# 6_power.net
KiCad netlist of a schematic drawn in Altium Designer
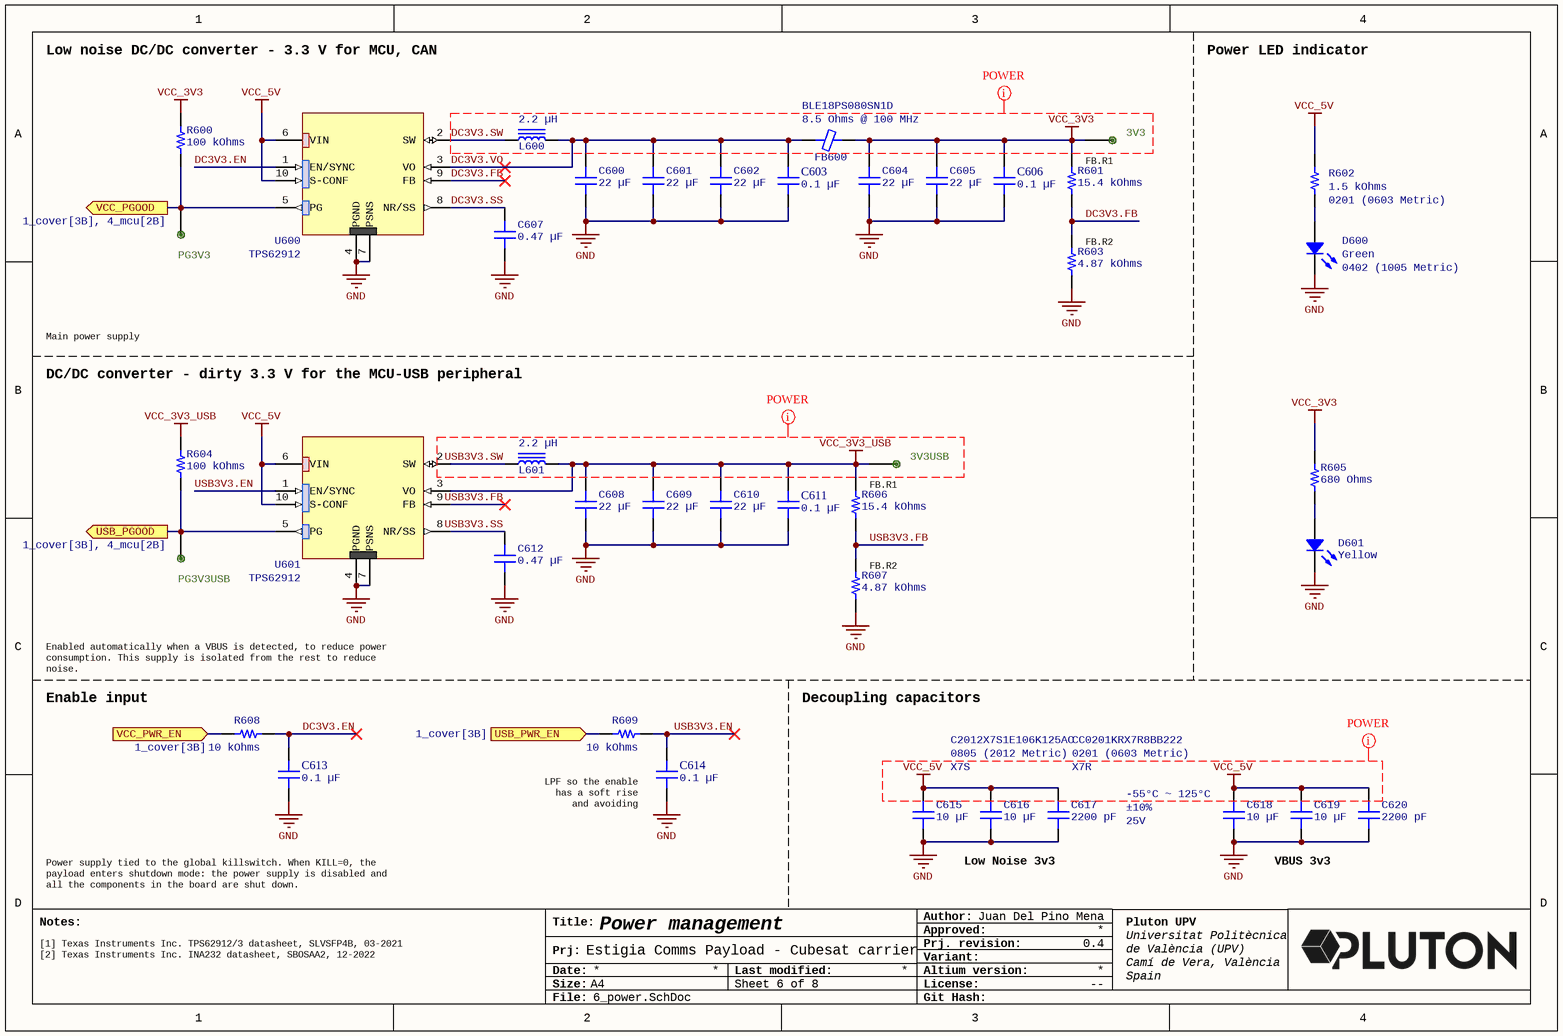
[diagram p0: 6_power.SchDoc]

(export (version "E")
  (design (tool "Eeschema 10.0.6"))
  (components
    (comp (ref "3V3")
      (value "~")
      (footprint "testpoints:testpoint_via")
      (description "Test point, thru-hole")
      (libsource (lib "testpoints") (part "TestPoint-VIA"))
    )
    (comp (ref "3V3USB")
      (value "~")
      (footprint "testpoints:testpoint_via")
      (description "Test point, thru-hole")
      (libsource (lib "testpoints") (part "TestPoint-VIA"))
    )
    (comp (ref "C600")
      (value "22 µF")
      (footprint "CAP 0805_2012")
      (description "CAP CER 22UF 10V X7S 0805")
      (fields
        (field (name "PART NUMBER") "C2012X7S1A226M125AC")
        (field (name "MANUFACTURER") "TDK Corporation")
      )
      (libsource (lib "Celestial Altium Library - altium_library") (part "Capacitor"))
    )
    (comp (ref "C601")
      (value "22 µF")
      (footprint "CAP 0805_2012")
      (description "CAP CER 22UF 10V X7S 0805")
      (fields
        (field (name "PART NUMBER") "C2012X7S1A226M125AC")
        (field (name "MANUFACTURER") "TDK Corporation")
      )
      (libsource (lib "Celestial Altium Library - altium_library") (part "Capacitor"))
    )
    (comp (ref "C602")
      (value "22 µF")
      (footprint "CAP 0805_2012")
      (description "CAP CER 22UF 10V X7S 0805")
      (fields
        (field (name "PART NUMBER") "C2012X7S1A226M125AC")
        (field (name "MANUFACTURER") "TDK Corporation")
      )
      (libsource (lib "Celestial Altium Library - altium_library") (part "Capacitor"))
    )
    (comp (ref "C603")
      (value "0.1 µF")
      (footprint "CAP 0402_1005")
      (description "CAP CER 0402 0.1UF 16V X7R 10%")
      (fields (field (name "PART NUMBER") "C0402C104K4RECAUTO") (field (name "MANUFACTURER") "KEMET"))
      (libsource (lib "Celestial Altium Library - altium_library") (part "Capacitor"))
    )
    (comp (ref "C604")
      (value "22 µF")
      (footprint "CAP 0805_2012")
      (description "CAP CER 22UF 10V X7S 0805")
      (fields
        (field (name "PART NUMBER") "C2012X7S1A226M125AC")
        (field (name "MANUFACTURER") "TDK Corporation")
      )
      (libsource (lib "Celestial Altium Library - altium_library") (part "Capacitor"))
    )
    (comp (ref "C605")
      (value "22 µF")
      (footprint "CAP 0805_2012")
      (description "CAP CER 22UF 10V X7S 0805")
      (fields
        (field (name "PART NUMBER") "C2012X7S1A226M125AC")
        (field (name "MANUFACTURER") "TDK Corporation")
      )
      (libsource (lib "Celestial Altium Library - altium_library") (part "Capacitor"))
    )
    (comp (ref "C606")
      (value "0.1 µF")
      (footprint "CAP 0402_1005")
      (description "CAP CER 0402 0.1UF 16V X7R 10%")
      (fields (field (name "PART NUMBER") "C0402C104K4RECAUTO") (field (name "MANUFACTURER") "KEMET"))
      (libsource (lib "Celestial Altium Library - altium_library") (part "Capacitor"))
    )
    (comp (ref "C607")
      (value "0.47 µF")
      (footprint "CAP 0402_1005")
      (description "CAP CER 0.47UF 16V X7S 0402")
      (fields
        (field (name "PART NUMBER") "CGA2B1X7S1C474K050BC")
        (field (name "MANUFACTURER") "TDK Corporation")
      )
      (libsource (lib "Celestial Altium Library - altium_library") (part "Capacitor"))
    )
    (comp (ref "C608")
      (value "22 µF")
      (footprint "CAP 0805_2012")
      (description "CAP CER 22UF 10V X7S 0805")
      (fields
        (field (name "PART NUMBER") "C2012X7S1A226M125AC")
        (field (name "MANUFACTURER") "TDK Corporation")
      )
      (libsource (lib "Celestial Altium Library - altium_library") (part "Capacitor"))
    )
    (comp (ref "C609")
      (value "22 µF")
      (footprint "CAP 0805_2012")
      (description "CAP CER 22UF 10V X7S 0805")
      (fields
        (field (name "PART NUMBER") "C2012X7S1A226M125AC")
        (field (name "MANUFACTURER") "TDK Corporation")
      )
      (libsource (lib "Celestial Altium Library - altium_library") (part "Capacitor"))
    )
    (comp (ref "C610")
      (value "22 µF")
      (footprint "CAP 0805_2012")
      (description "CAP CER 22UF 10V X7S 0805")
      (fields
        (field (name "PART NUMBER") "C2012X7S1A226M125AC")
        (field (name "MANUFACTURER") "TDK Corporation")
      )
      (libsource (lib "Celestial Altium Library - altium_library") (part "Capacitor"))
    )
    (comp (ref "C611")
      (value "0.1 µF")
      (footprint "CAP 0402_1005")
      (description "CAP CER 0402 0.1UF 16V X7R 10%")
      (fields (field (name "PART NUMBER") "C0402C104K4RECAUTO") (field (name "MANUFACTURER") "KEMET"))
      (libsource (lib "Celestial Altium Library - altium_library") (part "Capacitor"))
    )
    (comp (ref "C612")
      (value "0.47 µF")
      (footprint "CAP 0402_1005")
      (description "CAP CER 0.47UF 16V X7S 0402")
      (fields
        (field (name "PART NUMBER") "CGA2B1X7S1C474K050BC")
        (field (name "MANUFACTURER") "TDK Corporation")
      )
      (libsource (lib "Celestial Altium Library - altium_library") (part "Capacitor"))
    )
    (comp (ref "C613")
      (value "0.1 µF")
      (footprint "CAP 0402_1005")
      (description "CAP CER 0402 0.1UF 16V X7R 10%")
      (fields (field (name "PART NUMBER") "C0402C104K4RECAUTO") (field (name "MANUFACTURER") "KEMET"))
      (libsource (lib "Celestial Altium Library - altium_library") (part "Capacitor"))
    )
    (comp (ref "C614")
      (value "0.1 µF")
      (footprint "CAP 0402_1005")
      (description "CAP CER 0402 0.1UF 16V X7R 10%")
      (fields (field (name "PART NUMBER") "C0402C104K4RECAUTO") (field (name "MANUFACTURER") "KEMET"))
      (libsource (lib "Celestial Altium Library - altium_library") (part "Capacitor"))
    )
    (comp (ref "C615")
      (value "10 µF")
      (footprint "CAP 0805_2012")
      (description "CAP CER 10UF 25V X7S 0805")
      (fields
        (field (name "PART NUMBER") "C2012X7S1E106K125AC")
        (field (name "MANUFACTURER") "TDK Corporation")
      )
      (libsource (lib "Celestial Altium Library - altium_library") (part "Capacitor"))
    )
    (comp (ref "C616")
      (value "10 µF")
      (footprint "CAP 0805_2012")
      (description "CAP CER 10UF 25V X7S 0805")
      (fields
        (field (name "PART NUMBER") "C2012X7S1E106K125AC")
        (field (name "DEVICE PACKAGE") "0805 (2012 Metric)")
        (field (name "MANUFACTURER") "TDK Corporation")
        (field (name "TEMPERATURE COEFFICIENT") "X7S")
        (field (name "TOLERANCE") "±10%")
      )
      (libsource (lib "Celestial Altium Library - altium_library") (part "Capacitor"))
    )
    (comp (ref "C617")
      (value "2200 pF")
      (footprint "CAP 0201_0603")
      (description "CAP CER 2200PF 25V X7R 0201")
      (fields
        (field (name "PART NUMBER") "CC0201KRX7R8BB222")
        (field (name "DEVICE PACKAGE") "0201 (0603 Metric)")
        (field (name "MANUFACTURER") "Yageo")
        (field (name "OPERATING TEMPERATURE") "-55°C ~ 125°C")
        (field (name "TEMPERATURE COEFFICIENT") "X7R")
        (field (name "TOLERANCE") "±10%")
        (field (name "VOLTAGE - RATED") "25V")
      )
      (libsource (lib "Celestial Altium Library - altium_library") (part "Capacitor"))
    )
    (comp (ref "C618")
      (value "10 µF")
      (footprint "CAP 0805_2012")
      (description "CAP CER 10UF 25V X7S 0805")
      (fields
        (field (name "PART NUMBER") "C2012X7S1E106K125AC")
        (field (name "MANUFACTURER") "TDK Corporation")
      )
      (libsource (lib "Celestial Altium Library - altium_library") (part "Capacitor"))
    )
    (comp (ref "C619")
      (value "10 µF")
      (footprint "CAP 0805_2012")
      (description "CAP CER 10UF 25V X7S 0805")
      (fields
        (field (name "PART NUMBER") "C2012X7S1E106K125AC")
        (field (name "MANUFACTURER") "TDK Corporation")
      )
      (libsource (lib "Celestial Altium Library - altium_library") (part "Capacitor"))
    )
    (comp (ref "C620")
      (value "2200 pF")
      (footprint "CAP 0201_0603")
      (description "CAP CER 2200PF 25V X7R 0201")
      (fields (field (name "PART NUMBER") "CC0201KRX7R8BB222") (field (name "MANUFACTURER") "Yageo"))
      (libsource (lib "Celestial Altium Library - altium_library") (part "Capacitor"))
    )
    (comp (ref "D600")
      (value "Green")
      (footprint "LED 0402_1005 GREEN")
      (description "LED GREEN CLEAR 2SMD")
      (fields
        (field (name "PART NUMBER") "EAST10052GA0")
        (field (name "COLOR") "Green")
        (field (name "DEVICE PACKAGE") "0402 (1005 Metric)")
        (field (name "MANUFACTURER") "Everlight Electronics Co Ltd")
      )
      (libsource (lib "Celestial Altium Library - altium_library") (part "LED"))
    )
    (comp (ref "D601")
      (value "Yellow")
      (footprint "LED 0402_1005 YELLOW")
      (description "LED YELLOW CLEAR 1005 SMD")
      (fields
        (field (name "PART NUMBER") "FHY1105P-TR")
        (field (name "COLOR") "Yellow")
        (field (name "MANUFACTURER") "Stanley Electric Co")
      )
      (libsource (lib "Celestial Altium Library - altium_library") (part "LED"))
    )
    (comp (ref "FB600")
      (value "8.5 Ohms @ 100 MHz")
      (footprint "FER 0603_1608")
      (description "FERRITE BEAD 8.5 OHM 0603 1LN")
      (fields
        (field (name "PART NUMBER") "BLE18PS080SN1D")
        (field (name "IMPEDANCE @ FREQUENCY") "8.5 Ohms @ 100 MHz")
        (field (name "MANUFACTURER") "Murata Electronics")
      )
      (libsource (lib "Celestial Altium Library - altium_library") (part "Ferrite Chip"))
    )
    (comp (ref "L600")
      (value "2.2 µH")
      (footprint "BOURNS SRN4018")
      (description "FIXED IND 2.2UH 2.9A 44 MOHM SMD")
      (fields (field (name "PART NUMBER") "SRN4018-2R2M") (field (name "MANUFACTURER") "Bourns Inc."))
      (libsource (lib "Celestial Altium Library - altium_library") (part "Inductor"))
    )
    (comp (ref "L601")
      (value "2.2 µH")
      (footprint "BOURNS SRN4018")
      (description "FIXED IND 2.2UH 2.9A 44 MOHM SMD")
      (fields (field (name "PART NUMBER") "SRN4018-2R2M") (field (name "MANUFACTURER") "Bourns Inc."))
      (libsource (lib "Celestial Altium Library - altium_library") (part "Inductor"))
    )
    (comp (ref "PG3V3")
      (value "~")
      (footprint "testpoints:testpoint_via")
      (description "Test point, thru-hole")
      (libsource (lib "testpoints") (part "TestPoint-VIA"))
    )
    (comp (ref "PG3V3USB")
      (value "~")
      (footprint "testpoints:testpoint_via")
      (description "Test point, thru-hole")
      (libsource (lib "testpoints") (part "TestPoint-VIA"))
    )
    (comp (ref "R600")
      (value "100 kOhms")
      (footprint "RES 0201_0603")
      (description "RES 100K OHM 1% 1/20W 0201")
      (fields (field (name "PART NUMBER") "RC0201FR-13100KL") (field (name "MANUFACTURER") "Yageo"))
      (libsource (lib "Celestial Altium Library - altium_library") (part "Resistor"))
    )
    (comp (ref "R601")
      (value "15.4 kOhms")
      (footprint "RES 0201_0603")
      (description "RES 15.4K OHM 1% 1/20W 0201")
      (fields (field (name "PART NUMBER") "RC0201FR-0715K4L") (field (name "MANUFACTURER") "Yageo"))
      (libsource (lib "Celestial Altium Library - altium_library") (part "Resistor"))
    )
    (comp (ref "R602")
      (value "1.5 kOhms")
      (footprint "RES 0201_0603")
      (description "RES SMD 1.5K OHM 5% 1/20W 0201")
      (fields
        (field (name "PART NUMBER") "CRCW02011K50JNED")
        (field (name "DEVICE PACKAGE") "0201 (0603 Metric)")
        (field (name "MANUFACTURER") "Vishay Dale")
      )
      (libsource (lib "Celestial Altium Library - altium_library") (part "Resistor"))
    )
    (comp (ref "R603")
      (value "4.87 kOhms")
      (footprint "RES 0201_0603")
      (description "RES 4.87K OHM 1% 1/20W 0201")
      (fields (field (name "PART NUMBER") "RC0201FR-074K87L") (field (name "MANUFACTURER") "Yageo"))
      (libsource (lib "Celestial Altium Library - altium_library") (part "Resistor"))
    )
    (comp (ref "R604")
      (value "100 kOhms")
      (footprint "RES 0201_0603")
      (description "RES 100K OHM 1% 1/20W 0201")
      (fields (field (name "PART NUMBER") "RC0201FR-13100KL") (field (name "MANUFACTURER") "Yageo"))
      (libsource (lib "Celestial Altium Library - altium_library") (part "Resistor"))
    )
    (comp (ref "R605")
      (value "680 Ohms")
      (footprint "RES 0201_0603")
      (description "RES 680 OHM 5% 1/20W 0201")
      (fields (field (name "PART NUMBER") "RC0201JR-07680RL") (field (name "MANUFACTURER") "Yageo"))
      (libsource (lib "Celestial Altium Library - altium_library") (part "Resistor"))
    )
    (comp (ref "R606")
      (value "15.4 kOhms")
      (footprint "RES 0201_0603")
      (description "RES 15.4K OHM 1% 1/20W 0201")
      (fields (field (name "PART NUMBER") "RC0201FR-0715K4L") (field (name "MANUFACTURER") "Yageo"))
      (libsource (lib "Celestial Altium Library - altium_library") (part "Resistor"))
    )
    (comp (ref "R607")
      (value "4.87 kOhms")
      (footprint "RES 0201_0603")
      (description "RES 4.87K OHM 1% 1/20W 0201")
      (fields (field (name "PART NUMBER") "RC0201FR-074K87L") (field (name "MANUFACTURER") "Yageo"))
      (libsource (lib "Celestial Altium Library - altium_library") (part "Resistor"))
    )
    (comp (ref "R608")
      (value "10 kOhms")
      (footprint "RES 0201_0603")
      (description "RES SMD 10K OHM 1% 1/20W 0201")
      (fields (field (name "PART NUMBER") "AF0201FR-0710KL") (field (name "MANUFACTURER") "Yageo"))
      (libsource (lib "Celestial Altium Library - altium_library") (part "Resistor"))
    )
    (comp (ref "R609")
      (value "10 kOhms")
      (footprint "RES 0201_0603")
      (description "RES SMD 10K OHM 1% 1/20W 0201")
      (fields (field (name "PART NUMBER") "AF0201FR-0710KL") (field (name "MANUFACTURER") "Yageo"))
      (libsource (lib "Celestial Altium Library - altium_library") (part "Resistor"))
    )
    (comp (ref "U600")
      (value "TPS62912")
      (footprint "ics:VQFN-HR-TPS6291X")
      (libsource (lib "power") (part "TPS62912"))
    )
    (comp (ref "U601")
      (value "TPS62912")
      (footprint "ics:VQFN-HR-TPS6291X")
      (libsource (lib "power") (part "TPS62912"))
    )
  )
  (nets
    (net (code "1") (name "/DC3V3.EN") (class "Default")
      (node (ref "C613") (pin "2") (pinfunction "2_2") (pintype "passive"))
      (node (ref "R608") (pin "1") (pinfunction "1_1") (pintype "passive"))
      (node (ref "U600") (pin "1") (pinfunction "EN/SYNC_1") (pintype "input"))
    )
    (net (code "2") (name "/DC3V3.FB") (class "Default")
      (node (ref "R601") (pin "1") (pinfunction "1_1") (pintype "passive"))
      (node (ref "R603") (pin "2") (pinfunction "2_2") (pintype "passive"))
      (node (ref "U600") (pin "9") (pinfunction "FB_9") (pintype "input"))
    )
    (net (code "3") (name "/DC3V3.SS") (class "Default")
      (node (ref "C607") (pin "2") (pinfunction "2_2") (pintype "passive"))
      (node (ref "U600") (pin "8") (pinfunction "NR/SS_8") (pintype "output"))
    )
    (net (code "4") (name "/DC3V3.SW") (class "Default")
      (node (ref "L600") (pin "1") (pinfunction "1_1") (pintype "passive"))
      (node (ref "U600") (pin "2") (pinfunction "SW_2") (pintype "bidirectional"))
    )
    (net (code "6") (name "/DC3V3.VO") (class "Default")
      (node (ref "C600") (pin "2") (pinfunction "2_2") (pintype "passive"))
      (node (ref "C601") (pin "2") (pinfunction "2_2") (pintype "passive"))
      (node (ref "C602") (pin "2") (pinfunction "2_2") (pintype "passive"))
      (node (ref "C603") (pin "2") (pinfunction "2_2") (pintype "passive"))
      (node (ref "FB600") (pin "1") (pinfunction "1_1") (pintype "passive"))
      (node (ref "L600") (pin "2") (pinfunction "2_2") (pintype "passive"))
      (node (ref "U600") (pin "3") (pinfunction "VO_3") (pintype "input"))
    )
    (net (code "7") (name "/USB3V3.EN") (class "Default")
      (node (ref "C614") (pin "2") (pinfunction "2_2") (pintype "passive"))
      (node (ref "R609") (pin "1") (pinfunction "1_1") (pintype "passive"))
      (node (ref "U601") (pin "1") (pinfunction "EN/SYNC_1") (pintype "input"))
    )
    (net (code "8") (name "/USB3V3.FB") (class "Default")
      (node (ref "R606") (pin "1") (pinfunction "1_1") (pintype "passive"))
      (node (ref "R607") (pin "2") (pinfunction "2_2") (pintype "passive"))
      (node (ref "U601") (pin "9") (pinfunction "FB_9") (pintype "input"))
    )
    (net (code "9") (name "/USB3V3.SS") (class "Default")
      (node (ref "C612") (pin "2") (pinfunction "2_2") (pintype "passive"))
      (node (ref "U601") (pin "8") (pinfunction "NR/SS_8") (pintype "output"))
    )
    (net (code "10") (name "/USB3V3.SW") (class "Default")
      (node (ref "L601") (pin "1") (pinfunction "1_1") (pintype "passive"))
      (node (ref "U601") (pin "2") (pinfunction "SW_2") (pintype "bidirectional"))
    )
    (net (code "11") (name "/USB_PGOOD") (class "Default")
      (node (ref "PG3V3USB") (pin "0") (pinfunction "0_0") (pintype "passive"))
      (node (ref "R604") (pin "1") (pinfunction "1_1") (pintype "passive"))
      (node (ref "U601") (pin "5") (pinfunction "PG_5") (pintype "output"))
    )
    (net (code "12") (name "/USB_PWR_EN") (class "Default")
      (node (ref "R609") (pin "2") (pinfunction "2_2") (pintype "passive"))
    )
    (net (code "13") (name "/VCC_PGOOD") (class "Default")
      (node (ref "PG3V3") (pin "0") (pinfunction "0_0") (pintype "passive"))
      (node (ref "R600") (pin "1") (pinfunction "1_1") (pintype "passive"))
      (node (ref "U600") (pin "5") (pinfunction "PG_5") (pintype "output"))
    )
    (net (code "14") (name "/VCC_PWR_EN") (class "Default")
      (node (ref "R608") (pin "2") (pinfunction "2_2") (pintype "passive"))
    )
    (net (code "15") (name "GND") (class "Default")
      (node (ref "C600") (pin "1") (pinfunction "1_1") (pintype "passive"))
      (node (ref "C601") (pin "1") (pinfunction "1_1") (pintype "passive"))
      (node (ref "C602") (pin "1") (pinfunction "1_1") (pintype "passive"))
      (node (ref "C603") (pin "1") (pinfunction "1_1") (pintype "passive"))
      (node (ref "C604") (pin "1") (pinfunction "1_1") (pintype "passive"))
      (node (ref "C605") (pin "1") (pinfunction "1_1") (pintype "passive"))
      (node (ref "C606") (pin "1") (pinfunction "1_1") (pintype "passive"))
      (node (ref "C607") (pin "1") (pinfunction "1_1") (pintype "passive"))
      (node (ref "C608") (pin "1") (pinfunction "1_1") (pintype "passive"))
      (node (ref "C609") (pin "1") (pinfunction "1_1") (pintype "passive"))
      (node (ref "C610") (pin "1") (pinfunction "1_1") (pintype "passive"))
      (node (ref "C611") (pin "1") (pinfunction "1_1") (pintype "passive"))
      (node (ref "C612") (pin "1") (pinfunction "1_1") (pintype "passive"))
      (node (ref "C613") (pin "1") (pinfunction "1_1") (pintype "passive"))
      (node (ref "C614") (pin "1") (pinfunction "1_1") (pintype "passive"))
      (node (ref "C615") (pin "1") (pinfunction "1_1") (pintype "passive"))
      (node (ref "C616") (pin "1") (pinfunction "1_1") (pintype "passive"))
      (node (ref "C617") (pin "1") (pinfunction "1_1") (pintype "passive"))
      (node (ref "C618") (pin "1") (pinfunction "1_1") (pintype "passive"))
      (node (ref "C619") (pin "1") (pinfunction "1_1") (pintype "passive"))
      (node (ref "C620") (pin "1") (pinfunction "1_1") (pintype "passive"))
      (node (ref "D600") (pin "2") (pinfunction "2_2") (pintype "passive"))
      (node (ref "D601") (pin "2") (pinfunction "2_2") (pintype "passive"))
      (node (ref "R603") (pin "1") (pinfunction "1_1") (pintype "passive"))
      (node (ref "R607") (pin "1") (pinfunction "1_1") (pintype "passive"))
      (node (ref "U600") (pin "4") (pinfunction "PGND_4") (pintype "passive"))
      (node (ref "U600") (pin "7") (pinfunction "PSNS_7") (pintype "power_in"))
      (node (ref "U601") (pin "4") (pinfunction "PGND_4") (pintype "passive"))
      (node (ref "U601") (pin "7") (pinfunction "PSNS_7") (pintype "power_in"))
    )
    (net (code "16") (name "Net-(D600-Pad1)") (class "Default")
      (node (ref "D600") (pin "1") (pinfunction "1_1") (pintype "passive"))
      (node (ref "R602") (pin "1") (pinfunction "1_1") (pintype "passive"))
    )
    (net (code "17") (name "Net-(D601-Pad1)") (class "Default")
      (node (ref "D601") (pin "1") (pinfunction "1_1") (pintype "passive"))
      (node (ref "R605") (pin "1") (pinfunction "1_1") (pintype "passive"))
    )
    (net (code "18") (name "VCC_3V3") (class "Default")
      (node (ref "3V3") (pin "0") (pinfunction "0_0") (pintype "passive"))
      (node (ref "C604") (pin "2") (pinfunction "2_2") (pintype "passive"))
      (node (ref "C605") (pin "2") (pinfunction "2_2") (pintype "passive"))
      (node (ref "C606") (pin "2") (pinfunction "2_2") (pintype "passive"))
      (node (ref "FB600") (pin "2") (pinfunction "2_2") (pintype "passive"))
      (node (ref "R600") (pin "2") (pinfunction "2_2") (pintype "passive"))
      (node (ref "R601") (pin "2") (pinfunction "2_2") (pintype "passive"))
      (node (ref "R605") (pin "2") (pinfunction "2_2") (pintype "passive"))
    )
    (net (code "19") (name "VCC_3V3_USB") (class "Default")
      (node (ref "3V3USB") (pin "0") (pinfunction "0_0") (pintype "passive"))
      (node (ref "C608") (pin "2") (pinfunction "2_2") (pintype "passive"))
      (node (ref "C609") (pin "2") (pinfunction "2_2") (pintype "passive"))
      (node (ref "C610") (pin "2") (pinfunction "2_2") (pintype "passive"))
      (node (ref "C611") (pin "2") (pinfunction "2_2") (pintype "passive"))
      (node (ref "L601") (pin "2") (pinfunction "2_2") (pintype "passive"))
      (node (ref "R604") (pin "2") (pinfunction "2_2") (pintype "passive"))
      (node (ref "R606") (pin "2") (pinfunction "2_2") (pintype "passive"))
      (node (ref "U601") (pin "3") (pinfunction "VO_3") (pintype "input"))
    )
    (net (code "20") (name "VCC_5V") (class "Default")
      (node (ref "C615") (pin "2") (pinfunction "2_2") (pintype "passive"))
      (node (ref "C616") (pin "2") (pinfunction "2_2") (pintype "passive"))
      (node (ref "C617") (pin "2") (pinfunction "2_2") (pintype "passive"))
      (node (ref "C618") (pin "2") (pinfunction "2_2") (pintype "passive"))
      (node (ref "C619") (pin "2") (pinfunction "2_2") (pintype "passive"))
      (node (ref "C620") (pin "2") (pinfunction "2_2") (pintype "passive"))
      (node (ref "R602") (pin "2") (pinfunction "2_2") (pintype "passive"))
      (node (ref "U600") (pin "10") (pinfunction "S-CONF_10") (pintype "input"))
      (node (ref "U600") (pin "6") (pinfunction "VIN_6") (pintype "power_in"))
      (node (ref "U601") (pin "10") (pinfunction "S-CONF_10") (pintype "input"))
      (node (ref "U601") (pin "6") (pinfunction "VIN_6") (pintype "power_in"))
    )
  )
)
